# Schematic.net
KiCad netlist of a schematic drawn in Altium Designer
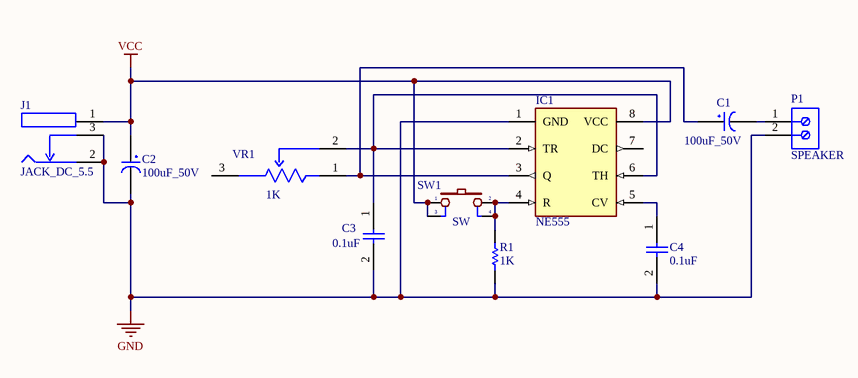
[diagram p0: Schematic.SchDoc]

(export (version "E")
  (design (tool "Eeschema 10.0.6"))
  (components
    (comp (ref "C1")
      (value "100uF_50V")
      (footprint "CAP_ELEC_100uF_50V")
      (description "Electrolytic Capacitor 100uF 50V")
      (libsource (lib "SachTran_Lib") (part "CAP_ELEC_100uF_50V"))
    )
    (comp (ref "C2")
      (value "100uF_50V")
      (footprint "CAP_ELEC_100uF_50V")
      (description "Electrolytic Capacitor 100uF 50V")
      (libsource (lib "") (part "CAP_ELEC_100uF_50V_1"))
    )
    (comp (ref "C3")
      (value "0.1uF")
      (footprint "CAP_CER_105")
      (description "Capacitor Ceramic 105 1uF")
      (libsource (lib "SachTran_Lib") (part "CAP_CER_105"))
    )
    (comp (ref "C4")
      (value "0.1uF")
      (footprint "CAP_CER_105")
      (description "Capacitor Ceramic 105 1uF")
      (libsource (lib "SachTran_Lib") (part "CAP_CER_105"))
    )
    (comp (ref "IC1")
      (value "NE555")
      (footprint "DIP8")
      (description "555 Type, Timer/Oscillator (Single) IC 500kHz 8-DIP")
      (libsource (lib "SachTran_Lib") (part "NE555"))
    )
    (comp (ref "J1")
      (value "JACK_DC_5.5")
      (footprint "DC5.5/2.1")
      (description "Jack DC 5.5x2.1")
      (libsource (lib "SachTran_Lib") (part "JACK_DC_5.5"))
    )
    (comp (ref "P1")
      (value "SPEAKER")
      (footprint "DOMINO_2")
      (description "Domino 2")
      (libsource (lib "SachTran_Lib") (part "DOMINO_2"))
    )
    (comp (ref "R1")
      (value "1K")
      (footprint "R1/4W")
      (description "Resistor Through-Hole  1K 1/4W")
      (libsource (lib "SachTran_Lib") (part "RES_1K_1/4W"))
    )
    (comp (ref "SW1")
      (value "SW")
      (footprint "SW4_2")
      (description "Switch button 4 pin")
      (libsource (lib "SachTran_Lib") (part "SW4"))
    )
    (comp (ref "VR1")
      (value "1K")
      (footprint "VR_VOLUME")
      (description "Variable_Resistor Volume 1K")
      (libsource (lib "SachTran_Lib") (part "VR_Volume 1K"))
    )
  )
  (nets
    (net (code "1") (name "GND") (class "Default")
      (node (ref "C2") (pin "2") (pinfunction "2_2") (pintype "passive"))
      (node (ref "C3") (pin "2") (pinfunction "2_2") (pintype "passive"))
      (node (ref "C4") (pin "2") (pinfunction "2_2") (pintype "passive"))
      (node (ref "IC1") (pin "1") (pinfunction "GND_1") (pintype "passive"))
      (node (ref "J1") (pin "2") (pinfunction "2_2") (pintype "passive"))
      (node (ref "J1") (pin "3") (pinfunction "3_3") (pintype "passive"))
      (node (ref "P1") (pin "2") (pinfunction "2_2") (pintype "passive"))
      (node (ref "R1") (pin "2") (pinfunction "2_2") (pintype "passive"))
    )
    (net (code "2") (name "Net-(C1-Pad2)") (class "Default")
      (node (ref "C1") (pin "2") (pinfunction "2_2") (pintype "passive"))
      (node (ref "P1") (pin "1") (pinfunction "1_1") (pintype "passive"))
    )
    (net (code "3") (name "Net-(IC1-CV)") (class "Default")
      (node (ref "C4") (pin "1") (pinfunction "1_1") (pintype "passive"))
      (node (ref "IC1") (pin "5") (pinfunction "CV_5") (pintype "input"))
    )
    (net (code "4") (name "Net-(IC1-Q)") (class "Default")
      (node (ref "C1") (pin "1") (pinfunction "1_1") (pintype "passive"))
      (node (ref "IC1") (pin "3") (pinfunction "Q_3") (pintype "output"))
      (node (ref "VR1") (pin "1") (pinfunction "1_1") (pintype "passive"))
    )
    (net (code "5") (name "Net-(IC1-R)") (class "Default")
      (node (ref "IC1") (pin "4") (pinfunction "R_4") (pintype "input"))
      (node (ref "R1") (pin "1") (pinfunction "1_1") (pintype "passive"))
      (node (ref "SW1") (pin "2") (pinfunction "2_2") (pintype "passive"))
      (node (ref "SW1") (pin "4") (pinfunction "4_4") (pintype "passive"))
    )
    (net (code "6") (name "Net-(IC1-TH)") (class "Default")
      (node (ref "C3") (pin "1") (pinfunction "1_1") (pintype "passive"))
      (node (ref "IC1") (pin "2") (pinfunction "TR_2") (pintype "input"))
      (node (ref "IC1") (pin "6") (pinfunction "TH_6") (pintype "input"))
      (node (ref "VR1") (pin "2") (pinfunction "2_2") (pintype "passive"))
    )
    (net (code "7") (name "VCC") (class "Default")
      (node (ref "C2") (pin "1") (pinfunction "1_1") (pintype "passive"))
      (node (ref "IC1") (pin "8") (pinfunction "VCC_8") (pintype "power_in"))
      (node (ref "J1") (pin "1") (pinfunction "1_1") (pintype "passive"))
      (node (ref "SW1") (pin "1") (pinfunction "1_1") (pintype "passive"))
      (node (ref "SW1") (pin "3") (pinfunction "3_3") (pintype "passive"))
    )
    (net (code "8") (name "unconnected-(IC1-DC-Pad7)") (class "Default")
      (node (ref "IC1") (pin "7") (pinfunction "DC_7") (pintype "output"))
    )
    (net (code "9") (name "unconnected-(VR1-Pad3)") (class "Default")
      (node (ref "VR1") (pin "3") (pinfunction "3_3") (pintype "passive"))
    )
  )
)
